# TDA7292.net
KiCad netlist of a schematic drawn in EAGLE
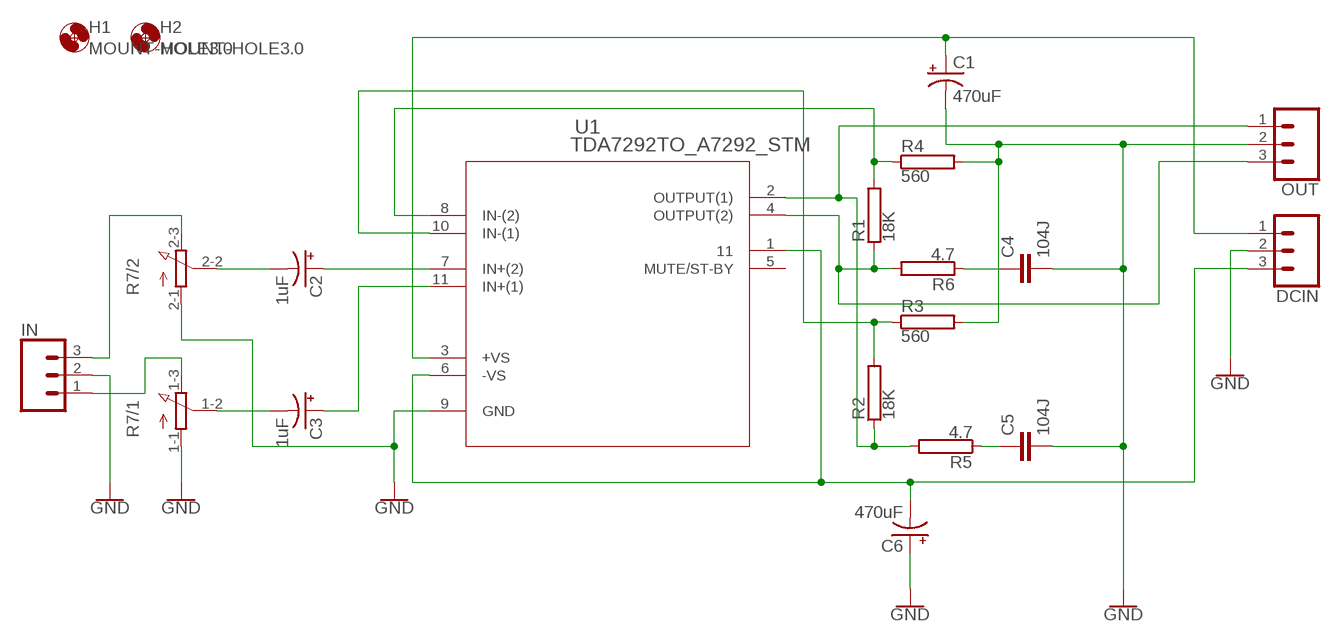
[diagram p0: schematic, sheet 1]

(export (version "E")
  (design (tool "Eeschema 10.0.6"))
  (components
    (comp (ref "C1")
      (value "470uF")
      (footprint "eagle-import:CPOL-RADIAL-5MM-10MM")
      (libsource (lib "eagle-import") (part "1000UF-RADIAL-5MM-25V-20%"))
    )
    (comp (ref "C2")
      (value "1uF")
      (footprint "eagle-import:CPOL-RADIAL-5MM-10MM")
      (libsource (lib "eagle-import") (part "1000UF-RADIAL-5MM-25V-20%"))
    )
    (comp (ref "C3")
      (value "1uF")
      (footprint "eagle-import:CPOL-RADIAL-5MM-10MM")
      (libsource (lib "eagle-import") (part "1000UF-RADIAL-5MM-25V-20%"))
    )
    (comp (ref "C4")
      (value "104J")
      (footprint "eagle-import:CAP-PTH-10MM")
      (libsource (lib "eagle-import") (part "10NF-PTH-10MM-10000V-1-%"))
    )
    (comp (ref "C5")
      (value "104J")
      (footprint "eagle-import:CAP-PTH-10MM")
      (libsource (lib "eagle-import") (part "10NF-PTH-10MM-10000V-1-%"))
    )
    (comp (ref "C6")
      (value "470uF")
      (footprint "eagle-import:CPOL-RADIAL-5MM-10MM")
      (libsource (lib "eagle-import") (part "1000UF-RADIAL-5MM-25V-20%"))
    )
    (comp (ref "DCIN")
      (value "CONN_03POLAR")
      (footprint "eagle-import:MOLEX-1X3")
      (libsource (lib "eagle-import") (part "CONN_03POLAR"))
    )
    (comp (ref "H1")
      (value "MOUNT-HOLE3.0")
      (footprint "eagle-import:3,0")
      (libsource (lib "eagle-import") (part "MOUNT-HOLE3.0"))
    )
    (comp (ref "H2")
      (value "MOUNT-HOLE3.0")
      (footprint "eagle-import:3,0")
      (libsource (lib "eagle-import") (part "MOUNT-HOLE3.0"))
    )
    (comp (ref "IN")
      (value "CONN_03POLAR")
      (footprint "eagle-import:MOLEX-1X3")
      (libsource (lib "eagle-import") (part "CONN_03POLAR"))
    )
    (comp (ref "OUT")
      (value "CONN_03POLAR")
      (footprint "eagle-import:MOLEX-1X3")
      (libsource (lib "eagle-import") (part "CONN_03POLAR"))
    )
    (comp (ref "R1")
      (value "18K")
      (footprint "eagle-import:RS1_2")
      (fields (field (name "MF") "OHMITE") (field (name "MPN") "RRS1K0E"))
      (libsource (lib "eagle-import") (part "RRS1/2"))
    )
    (comp (ref "R2")
      (value "18K")
      (footprint "eagle-import:RS1_2")
      (fields (field (name "MF") "OHMITE") (field (name "MPN") "RRS1K0E"))
      (libsource (lib "eagle-import") (part "RRS1/2"))
    )
    (comp (ref "R3")
      (value "560")
      (footprint "eagle-import:RS1_2")
      (fields (field (name "MF") "OHMITE") (field (name "MPN") "RRS1K0E"))
      (libsource (lib "eagle-import") (part "RRS1/2"))
    )
    (comp (ref "R4")
      (value "560")
      (footprint "eagle-import:RS1_2")
      (fields (field (name "MF") "OHMITE") (field (name "MPN") "RRS1K0E"))
      (libsource (lib "eagle-import") (part "RRS1/2"))
    )
    (comp (ref "R5")
      (value "4.7")
      (footprint "eagle-import:RS1_2")
      (fields (field (name "MF") "OHMITE") (field (name "MPN") "RRS1K0E"))
      (libsource (lib "eagle-import") (part "RRS1/2"))
    )
    (comp (ref "R6")
      (value "4.7")
      (footprint "eagle-import:RS1_2")
      (fields (field (name "MF") "OHMITE") (field (name "MPN") "RRS1K0E"))
      (libsource (lib "eagle-import") (part "RRS1/2"))
    )
    (comp (ref "R7")
      (value "3RP/1610G")
      (footprint "eagle-import:3RP_1610G")
      (libsource (lib "eagle-import") (part "3RP/1610G"))
    )
    (comp (ref "U1")
      (value "TDA7292TO_A7292_STM")
      (footprint "eagle-import:TO_A7292_STM")
      (fields
        (field (name "MANUFACTURER_PART_NUMBER") "TDA7292")
        (field (name "COPYRIGHT") "Copyright (C) 2022 Ultra Librarian. All rights reserved.")
      )
      (libsource (lib "eagle-import") (part "TDA7292TO_A7292_STM"))
    )
  )
  (nets
    (net (code "1") (name "GND") (class "Default")
      (node (ref "C1") (pin "-") (pinfunction "-_-") (pintype "passive"))
      (node (ref "C4") (pin "2") (pinfunction "2_2") (pintype "passive"))
      (node (ref "C5") (pin "2") (pinfunction "2_2") (pintype "passive"))
      (node (ref "C6") (pin "+") (pinfunction "+_+") (pintype "passive"))
      (node (ref "DCIN") (pin "2") (pinfunction "2_2") (pintype "passive"))
      (node (ref "IN") (pin "2") (pinfunction "2_2") (pintype "passive"))
      (node (ref "OUT") (pin "2") (pinfunction "2_2") (pintype "passive"))
      (node (ref "R3") (pin "2") (pinfunction "2_2") (pintype "passive"))
      (node (ref "R4") (pin "2") (pinfunction "2_2") (pintype "passive"))
      (node (ref "R7") (pin "1-1") (pinfunction "A_1-1") (pintype "passive"))
      (node (ref "R7") (pin "2-1") (pinfunction "A_2-1") (pintype "passive"))
      (node (ref "U1") (pin "9") (pinfunction "GND_9") (pintype "passive"))
    )
    (net (code "2") (name "Net-(C4-Pad1)") (class "Default")
      (node (ref "C4") (pin "1") (pinfunction "1_1") (pintype "passive"))
      (node (ref "R6") (pin "1") (pinfunction "1_1") (pintype "passive"))
    )
    (net (code "3") (name "Net-(C5-Pad1)") (class "Default")
      (node (ref "C5") (pin "1") (pinfunction "1_1") (pintype "passive"))
      (node (ref "R5") (pin "1") (pinfunction "1_1") (pintype "passive"))
    )
    (net (code "4") (name "Net-(R7A-E)") (class "Default")
      (node (ref "IN") (pin "1") (pinfunction "1_1") (pintype "passive"))
      (node (ref "R7") (pin "1-3") (pinfunction "E_1-3") (pintype "passive"))
    )
    (net (code "5") (name "Net-(R7A-S)") (class "Default")
      (node (ref "C3") (pin "-") (pinfunction "-_-") (pintype "passive"))
      (node (ref "R7") (pin "1-2") (pinfunction "S_1-2") (pintype "passive"))
    )
    (net (code "6") (name "Net-(R7B-E)") (class "Default")
      (node (ref "IN") (pin "3") (pinfunction "3_3") (pintype "passive"))
      (node (ref "R7") (pin "2-3") (pinfunction "E_2-3") (pintype "passive"))
    )
    (net (code "7") (name "Net-(R7B-S)") (class "Default")
      (node (ref "C2") (pin "-") (pinfunction "-_-") (pintype "passive"))
      (node (ref "R7") (pin "2-2") (pinfunction "S_2-2") (pintype "passive"))
    )
    (net (code "8") (name "Net-(U1-+VS)") (class "Default")
      (node (ref "C1") (pin "+") (pinfunction "+_+") (pintype "passive"))
      (node (ref "DCIN") (pin "1") (pinfunction "1_1") (pintype "passive"))
      (node (ref "U1") (pin "3") (pinfunction "+VS_3") (pintype "power_in"))
    )
    (net (code "9") (name "Net-(U1--VS)") (class "Default")
      (node (ref "C6") (pin "-") (pinfunction "-_-") (pintype "passive"))
      (node (ref "DCIN") (pin "3") (pinfunction "3_3") (pintype "passive"))
      (node (ref "U1") (pin "1") (pinfunction "11_1") (pintype "passive"))
      (node (ref "U1") (pin "6") (pinfunction "-VS_6") (pintype "power_in"))
    )
    (net (code "10") (name "Net-(U1-IN+(1))") (class "Default")
      (node (ref "C3") (pin "+") (pinfunction "+_+") (pintype "passive"))
      (node (ref "U1") (pin "11") (pinfunction "IN+(1)_11") (pintype "input"))
    )
    (net (code "11") (name "Net-(U1-IN+(2))") (class "Default")
      (node (ref "C2") (pin "+") (pinfunction "+_+") (pintype "passive"))
      (node (ref "U1") (pin "7") (pinfunction "IN+(2)_7") (pintype "input"))
    )
    (net (code "12") (name "Net-(U1-IN-(1))") (class "Default")
      (node (ref "R2") (pin "2") (pinfunction "2_2") (pintype "passive"))
      (node (ref "R3") (pin "1") (pinfunction "1_1") (pintype "passive"))
      (node (ref "U1") (pin "10") (pinfunction "IN-(1)_10") (pintype "input"))
    )
    (net (code "13") (name "Net-(U1-IN-(2))") (class "Default")
      (node (ref "R1") (pin "2") (pinfunction "2_2") (pintype "passive"))
      (node (ref "R4") (pin "1") (pinfunction "1_1") (pintype "passive"))
      (node (ref "U1") (pin "8") (pinfunction "IN-(2)_8") (pintype "input"))
    )
    (net (code "14") (name "Net-(U1-OUTPUT(1))") (class "Default")
      (node (ref "OUT") (pin "1") (pinfunction "1_1") (pintype "passive"))
      (node (ref "R2") (pin "1") (pinfunction "1_1") (pintype "passive"))
      (node (ref "R5") (pin "2") (pinfunction "2_2") (pintype "passive"))
      (node (ref "U1") (pin "2") (pinfunction "OUTPUT(1)_2") (pintype "output"))
    )
    (net (code "15") (name "Net-(U1-OUTPUT(2))") (class "Default")
      (node (ref "OUT") (pin "3") (pinfunction "3_3") (pintype "passive"))
      (node (ref "R1") (pin "1") (pinfunction "1_1") (pintype "passive"))
      (node (ref "R6") (pin "2") (pinfunction "2_2") (pintype "passive"))
      (node (ref "U1") (pin "4") (pinfunction "OUTPUT(2)_4") (pintype "output"))
    )
    (net (code "16") (name "unconnected-(U1-MUTE{slash}ST-BY-Pad5)") (class "Default")
      (node (ref "U1") (pin "5") (pinfunction "MUTE/ST-BY_5") (pintype "passive"))
    )
  )
)
